# Schematic.net
KiCad netlist of a schematic drawn in EAGLE
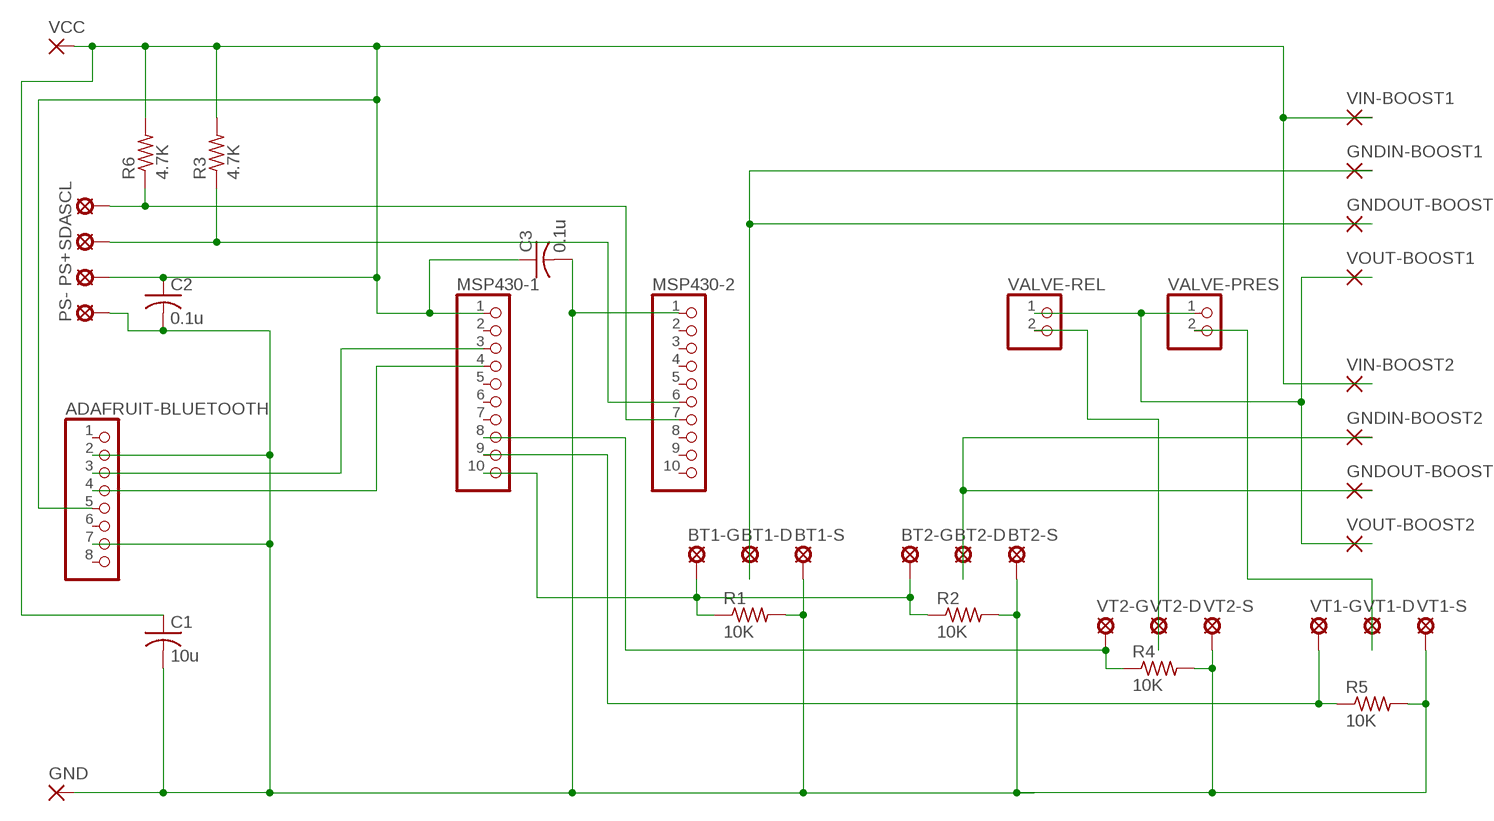
[diagram p0: schematic, sheet 1]

(export (version "E")
  (design (tool "Eeschema 10.0.6"))
  (components
    (comp (ref "ADAFRUIT-BLUETOOTH")
      (value "PINHD-1X8")
      (footprint "eagle-import:1X08")
      (libsource (lib "eagle-import") (part "PINHD-1X8"))
    )
    (comp (ref "BT1-D")
      (value "LSP10")
      (footprint "eagle-import:LSP10")
      (libsource (lib "eagle-import") (part "LSP10"))
    )
    (comp (ref "BT1-G")
      (value "LSP10")
      (footprint "eagle-import:LSP10")
      (libsource (lib "eagle-import") (part "LSP10"))
    )
    (comp (ref "BT1-S")
      (value "LSP10")
      (footprint "eagle-import:LSP10")
      (libsource (lib "eagle-import") (part "LSP10"))
    )
    (comp (ref "BT2-D")
      (value "LSP10")
      (footprint "eagle-import:LSP10")
      (libsource (lib "eagle-import") (part "LSP10"))
    )
    (comp (ref "BT2-G")
      (value "LSP10")
      (footprint "eagle-import:LSP10")
      (libsource (lib "eagle-import") (part "LSP10"))
    )
    (comp (ref "BT2-S")
      (value "LSP10")
      (footprint "eagle-import:LSP10")
      (libsource (lib "eagle-import") (part "LSP10"))
    )
    (comp (ref "C1")
      (value "10u")
      (footprint "eagle-import:C0805")
      (libsource (lib "eagle-import") (part "C-USC0805"))
    )
    (comp (ref "C2")
      (value "0.1u")
      (footprint "eagle-import:C0805")
      (libsource (lib "eagle-import") (part "C-USC0805"))
    )
    (comp (ref "C3")
      (value "0.1u")
      (footprint "eagle-import:C0805")
      (libsource (lib "eagle-import") (part "C-USC0805"))
    )
    (comp (ref "GND")
      (value "SMD5")
      (footprint "eagle-import:SMD2,54-5,08")
      (libsource (lib "eagle-import") (part "SMD5"))
    )
    (comp (ref "GNDIN-BOOST1")
      (value "SMD5")
      (footprint "eagle-import:SMD2,54-5,08")
      (libsource (lib "eagle-import") (part "SMD5"))
    )
    (comp (ref "GNDIN-BOOST2")
      (value "SMD5")
      (footprint "eagle-import:SMD2,54-5,08")
      (libsource (lib "eagle-import") (part "SMD5"))
    )
    (comp (ref "GNDOUT-BOOST1")
      (value "SMD5")
      (footprint "eagle-import:SMD2,54-5,08")
      (libsource (lib "eagle-import") (part "SMD5"))
    )
    (comp (ref "GNDOUT-BOOST2")
      (value "SMD5")
      (footprint "eagle-import:SMD2,54-5,08")
      (libsource (lib "eagle-import") (part "SMD5"))
    )
    (comp (ref "MSP430-1")
      (value "PINHD-1X10")
      (footprint "eagle-import:1X10")
      (libsource (lib "eagle-import") (part "PINHD-1X10"))
    )
    (comp (ref "MSP430-2")
      (value "PINHD-1X10")
      (footprint "eagle-import:1X10")
      (libsource (lib "eagle-import") (part "PINHD-1X10"))
    )
    (comp (ref "PS+")
      (value "LSP10")
      (footprint "eagle-import:LSP10")
      (libsource (lib "eagle-import") (part "LSP10"))
    )
    (comp (ref "PS-")
      (value "LSP10")
      (footprint "eagle-import:LSP10")
      (libsource (lib "eagle-import") (part "LSP10"))
    )
    (comp (ref "R1")
      (value "10K")
      (footprint "eagle-import:0309_12")
      (libsource (lib "eagle-import") (part "R-US_0309/12"))
    )
    (comp (ref "R2")
      (value "10K")
      (footprint "eagle-import:0309_12")
      (libsource (lib "eagle-import") (part "R-US_0309/12"))
    )
    (comp (ref "R3")
      (value "4.7K")
      (footprint "eagle-import:0309_12")
      (libsource (lib "eagle-import") (part "R-US_0309/12"))
    )
    (comp (ref "R4")
      (value "10K")
      (footprint "eagle-import:0309_12")
      (libsource (lib "eagle-import") (part "R-US_0309/12"))
    )
    (comp (ref "R5")
      (value "10K")
      (footprint "eagle-import:0309_12")
      (libsource (lib "eagle-import") (part "R-US_0309/12"))
    )
    (comp (ref "R6")
      (value "4.7K")
      (footprint "eagle-import:0309_12")
      (libsource (lib "eagle-import") (part "R-US_0309/12"))
    )
    (comp (ref "SCL")
      (value "LSP10")
      (footprint "eagle-import:LSP10")
      (libsource (lib "eagle-import") (part "LSP10"))
    )
    (comp (ref "SDA")
      (value "LSP10")
      (footprint "eagle-import:LSP10")
      (libsource (lib "eagle-import") (part "LSP10"))
    )
    (comp (ref "VALVE-PRES")
      (value "PINHD-1X2")
      (footprint "eagle-import:1X02")
      (libsource (lib "eagle-import") (part "PINHD-1X2"))
    )
    (comp (ref "VALVE-REL")
      (value "PINHD-1X2")
      (footprint "eagle-import:1X02")
      (libsource (lib "eagle-import") (part "PINHD-1X2"))
    )
    (comp (ref "VCC")
      (value "SMD5")
      (footprint "eagle-import:SMD2,54-5,08")
      (libsource (lib "eagle-import") (part "SMD5"))
    )
    (comp (ref "VIN-BOOST1")
      (value "SMD5")
      (footprint "eagle-import:SMD2,54-5,08")
      (libsource (lib "eagle-import") (part "SMD5"))
    )
    (comp (ref "VIN-BOOST2")
      (value "SMD5")
      (footprint "eagle-import:SMD2,54-5,08")
      (libsource (lib "eagle-import") (part "SMD5"))
    )
    (comp (ref "VOUT-BOOST1")
      (value "SMD5")
      (footprint "eagle-import:SMD2,54-5,08")
      (libsource (lib "eagle-import") (part "SMD5"))
    )
    (comp (ref "VOUT-BOOST2")
      (value "SMD5")
      (footprint "eagle-import:SMD2,54-5,08")
      (libsource (lib "eagle-import") (part "SMD5"))
    )
    (comp (ref "VT1-D")
      (value "LSP10")
      (footprint "eagle-import:LSP10")
      (libsource (lib "eagle-import") (part "LSP10"))
    )
    (comp (ref "VT1-G")
      (value "LSP10")
      (footprint "eagle-import:LSP10")
      (libsource (lib "eagle-import") (part "LSP10"))
    )
    (comp (ref "VT1-S")
      (value "LSP10")
      (footprint "eagle-import:LSP10")
      (libsource (lib "eagle-import") (part "LSP10"))
    )
    (comp (ref "VT2-D")
      (value "LSP10")
      (footprint "eagle-import:LSP10")
      (libsource (lib "eagle-import") (part "LSP10"))
    )
    (comp (ref "VT2-G")
      (value "LSP10")
      (footprint "eagle-import:LSP10")
      (libsource (lib "eagle-import") (part "LSP10"))
    )
    (comp (ref "VT2-S")
      (value "LSP10")
      (footprint "eagle-import:LSP10")
      (libsource (lib "eagle-import") (part "LSP10"))
    )
  )
  (nets
    (net (code "1") (name "Net-(ADAFRUIT-BLUETOOTH-Pad3)") (class "Default")
      (node (ref "ADAFRUIT-BLUETOOTH") (pin "3") (pinfunction "3_3") (pintype "passive"))
      (node (ref "MSP430-1") (pin "3") (pinfunction "3_3") (pintype "passive"))
    )
    (net (code "2") (name "Net-(ADAFRUIT-BLUETOOTH-Pad4)") (class "Default")
      (node (ref "ADAFRUIT-BLUETOOTH") (pin "4") (pinfunction "4_4") (pintype "passive"))
      (node (ref "MSP430-1") (pin "4") (pinfunction "4_4") (pintype "passive"))
    )
    (net (code "3") (name "Net-(BT1-G-PadMP)") (class "Default")
      (node (ref "BT1-G") (pin "MP") (pinfunction "MP_MP") (pintype "passive"))
      (node (ref "BT2-G") (pin "MP") (pinfunction "MP_MP") (pintype "passive"))
      (node (ref "MSP430-1") (pin "10") (pinfunction "10_10") (pintype "passive"))
      (node (ref "R1") (pin "1") (pinfunction "1_1") (pintype "passive"))
      (node (ref "R2") (pin "1") (pinfunction "1_1") (pintype "passive"))
    )
    (net (code "4") (name "Net-(GND-P)") (class "Default")
      (node (ref "ADAFRUIT-BLUETOOTH") (pin "2") (pinfunction "2_2") (pintype "passive"))
      (node (ref "ADAFRUIT-BLUETOOTH") (pin "7") (pinfunction "7_7") (pintype "passive"))
      (node (ref "BT1-S") (pin "MP") (pinfunction "MP_MP") (pintype "passive"))
      (node (ref "BT2-S") (pin "MP") (pinfunction "MP_MP") (pintype "passive"))
      (node (ref "C1") (pin "2") (pinfunction "2_2") (pintype "passive"))
      (node (ref "C2") (pin "2") (pinfunction "2_2") (pintype "passive"))
      (node (ref "C3") (pin "2") (pinfunction "2_2") (pintype "passive"))
      (node (ref "GND") (pin "1") (pinfunction "P_1") (pintype "passive"))
      (node (ref "MSP430-2") (pin "1") (pinfunction "1_1") (pintype "passive"))
      (node (ref "PS-") (pin "MP") (pinfunction "MP_MP") (pintype "passive"))
      (node (ref "R1") (pin "2") (pinfunction "2_2") (pintype "passive"))
      (node (ref "R2") (pin "2") (pinfunction "2_2") (pintype "passive"))
      (node (ref "R4") (pin "2") (pinfunction "2_2") (pintype "passive"))
      (node (ref "R5") (pin "2") (pinfunction "2_2") (pintype "passive"))
      (node (ref "VT1-S") (pin "MP") (pinfunction "MP_MP") (pintype "passive"))
      (node (ref "VT2-S") (pin "MP") (pinfunction "MP_MP") (pintype "passive"))
    )
    (net (code "5") (name "Net-(GNDIN-BOOST1-P)") (class "Default")
      (node (ref "BT1-D") (pin "MP") (pinfunction "MP_MP") (pintype "passive"))
      (node (ref "GNDIN-BOOST1") (pin "1") (pinfunction "P_1") (pintype "passive"))
      (node (ref "GNDOUT-BOOST1") (pin "1") (pinfunction "P_1") (pintype "passive"))
    )
    (net (code "6") (name "Net-(GNDIN-BOOST2-P)") (class "Default")
      (node (ref "BT2-D") (pin "MP") (pinfunction "MP_MP") (pintype "passive"))
      (node (ref "GNDIN-BOOST2") (pin "1") (pinfunction "P_1") (pintype "passive"))
      (node (ref "GNDOUT-BOOST2") (pin "1") (pinfunction "P_1") (pintype "passive"))
    )
    (net (code "7") (name "Net-(MSP430-1-Pad8)") (class "Default")
      (node (ref "MSP430-1") (pin "8") (pinfunction "8_8") (pintype "passive"))
      (node (ref "R4") (pin "1") (pinfunction "1_1") (pintype "passive"))
      (node (ref "VT2-G") (pin "MP") (pinfunction "MP_MP") (pintype "passive"))
    )
    (net (code "8") (name "Net-(MSP430-1-Pad9)") (class "Default")
      (node (ref "MSP430-1") (pin "9") (pinfunction "9_9") (pintype "passive"))
      (node (ref "R5") (pin "1") (pinfunction "1_1") (pintype "passive"))
      (node (ref "VT1-G") (pin "MP") (pinfunction "MP_MP") (pintype "passive"))
    )
    (net (code "9") (name "Net-(MSP430-2-Pad6)") (class "Default")
      (node (ref "MSP430-2") (pin "6") (pinfunction "6_6") (pintype "passive"))
      (node (ref "R3") (pin "1") (pinfunction "1_1") (pintype "passive"))
      (node (ref "SDA") (pin "MP") (pinfunction "MP_MP") (pintype "passive"))
    )
    (net (code "10") (name "Net-(MSP430-2-Pad7)") (class "Default")
      (node (ref "MSP430-2") (pin "7") (pinfunction "7_7") (pintype "passive"))
      (node (ref "R6") (pin "1") (pinfunction "1_1") (pintype "passive"))
      (node (ref "SCL") (pin "MP") (pinfunction "MP_MP") (pintype "passive"))
    )
    (net (code "11") (name "Net-(VALVE-PRES-Pad2)") (class "Default")
      (node (ref "VALVE-PRES") (pin "2") (pinfunction "2_2") (pintype "passive"))
      (node (ref "VT1-D") (pin "MP") (pinfunction "MP_MP") (pintype "passive"))
    )
    (net (code "12") (name "Net-(VALVE-REL-Pad2)") (class "Default")
      (node (ref "VALVE-REL") (pin "2") (pinfunction "2_2") (pintype "passive"))
      (node (ref "VT2-D") (pin "MP") (pinfunction "MP_MP") (pintype "passive"))
    )
    (net (code "13") (name "Net-(VCC-P)") (class "Default")
      (node (ref "ADAFRUIT-BLUETOOTH") (pin "5") (pinfunction "5_5") (pintype "passive"))
      (node (ref "C1") (pin "1") (pinfunction "1_1") (pintype "passive"))
      (node (ref "C2") (pin "1") (pinfunction "1_1") (pintype "passive"))
      (node (ref "C3") (pin "1") (pinfunction "1_1") (pintype "passive"))
      (node (ref "MSP430-1") (pin "1") (pinfunction "1_1") (pintype "passive"))
      (node (ref "PS+") (pin "MP") (pinfunction "MP_MP") (pintype "passive"))
      (node (ref "R3") (pin "2") (pinfunction "2_2") (pintype "passive"))
      (node (ref "R6") (pin "2") (pinfunction "2_2") (pintype "passive"))
      (node (ref "VCC") (pin "1") (pinfunction "P_1") (pintype "passive"))
      (node (ref "VIN-BOOST1") (pin "1") (pinfunction "P_1") (pintype "passive"))
      (node (ref "VIN-BOOST2") (pin "1") (pinfunction "P_1") (pintype "passive"))
    )
    (net (code "14") (name "Net-(VOUT-BOOST1-P)") (class "Default")
      (node (ref "VALVE-PRES") (pin "1") (pinfunction "1_1") (pintype "passive"))
      (node (ref "VALVE-REL") (pin "1") (pinfunction "1_1") (pintype "passive"))
      (node (ref "VOUT-BOOST1") (pin "1") (pinfunction "P_1") (pintype "passive"))
      (node (ref "VOUT-BOOST2") (pin "1") (pinfunction "P_1") (pintype "passive"))
    )
    (net (code "15") (name "unconnected-(ADAFRUIT-BLUETOOTH-Pad1)") (class "Default")
      (node (ref "ADAFRUIT-BLUETOOTH") (pin "1") (pinfunction "1_1") (pintype "passive"))
    )
    (net (code "16") (name "unconnected-(ADAFRUIT-BLUETOOTH-Pad6)") (class "Default")
      (node (ref "ADAFRUIT-BLUETOOTH") (pin "6") (pinfunction "6_6") (pintype "passive"))
    )
    (net (code "17") (name "unconnected-(ADAFRUIT-BLUETOOTH-Pad8)") (class "Default")
      (node (ref "ADAFRUIT-BLUETOOTH") (pin "8") (pinfunction "8_8") (pintype "passive"))
    )
    (net (code "18") (name "unconnected-(MSP430-1-Pad2)") (class "Default")
      (node (ref "MSP430-1") (pin "2") (pinfunction "2_2") (pintype "passive"))
    )
    (net (code "19") (name "unconnected-(MSP430-1-Pad5)") (class "Default")
      (node (ref "MSP430-1") (pin "5") (pinfunction "5_5") (pintype "passive"))
    )
    (net (code "20") (name "unconnected-(MSP430-1-Pad6)") (class "Default")
      (node (ref "MSP430-1") (pin "6") (pinfunction "6_6") (pintype "passive"))
    )
    (net (code "21") (name "unconnected-(MSP430-1-Pad7)") (class "Default")
      (node (ref "MSP430-1") (pin "7") (pinfunction "7_7") (pintype "passive"))
    )
    (net (code "22") (name "unconnected-(MSP430-2-Pad2)") (class "Default")
      (node (ref "MSP430-2") (pin "2") (pinfunction "2_2") (pintype "passive"))
    )
    (net (code "23") (name "unconnected-(MSP430-2-Pad3)") (class "Default")
      (node (ref "MSP430-2") (pin "3") (pinfunction "3_3") (pintype "passive"))
    )
    (net (code "24") (name "unconnected-(MSP430-2-Pad4)") (class "Default")
      (node (ref "MSP430-2") (pin "4") (pinfunction "4_4") (pintype "passive"))
    )
    (net (code "25") (name "unconnected-(MSP430-2-Pad5)") (class "Default")
      (node (ref "MSP430-2") (pin "5") (pinfunction "5_5") (pintype "passive"))
    )
    (net (code "26") (name "unconnected-(MSP430-2-Pad8)") (class "Default")
      (node (ref "MSP430-2") (pin "8") (pinfunction "8_8") (pintype "passive"))
    )
    (net (code "27") (name "unconnected-(MSP430-2-Pad9)") (class "Default")
      (node (ref "MSP430-2") (pin "9") (pinfunction "9_9") (pintype "passive"))
    )
    (net (code "28") (name "unconnected-(MSP430-2-Pad10)") (class "Default")
      (node (ref "MSP430-2") (pin "10") (pinfunction "10_10") (pintype "passive"))
    )
  )
)
